# circuit.net
KiCad netlist of a schematic drawn in EAGLE
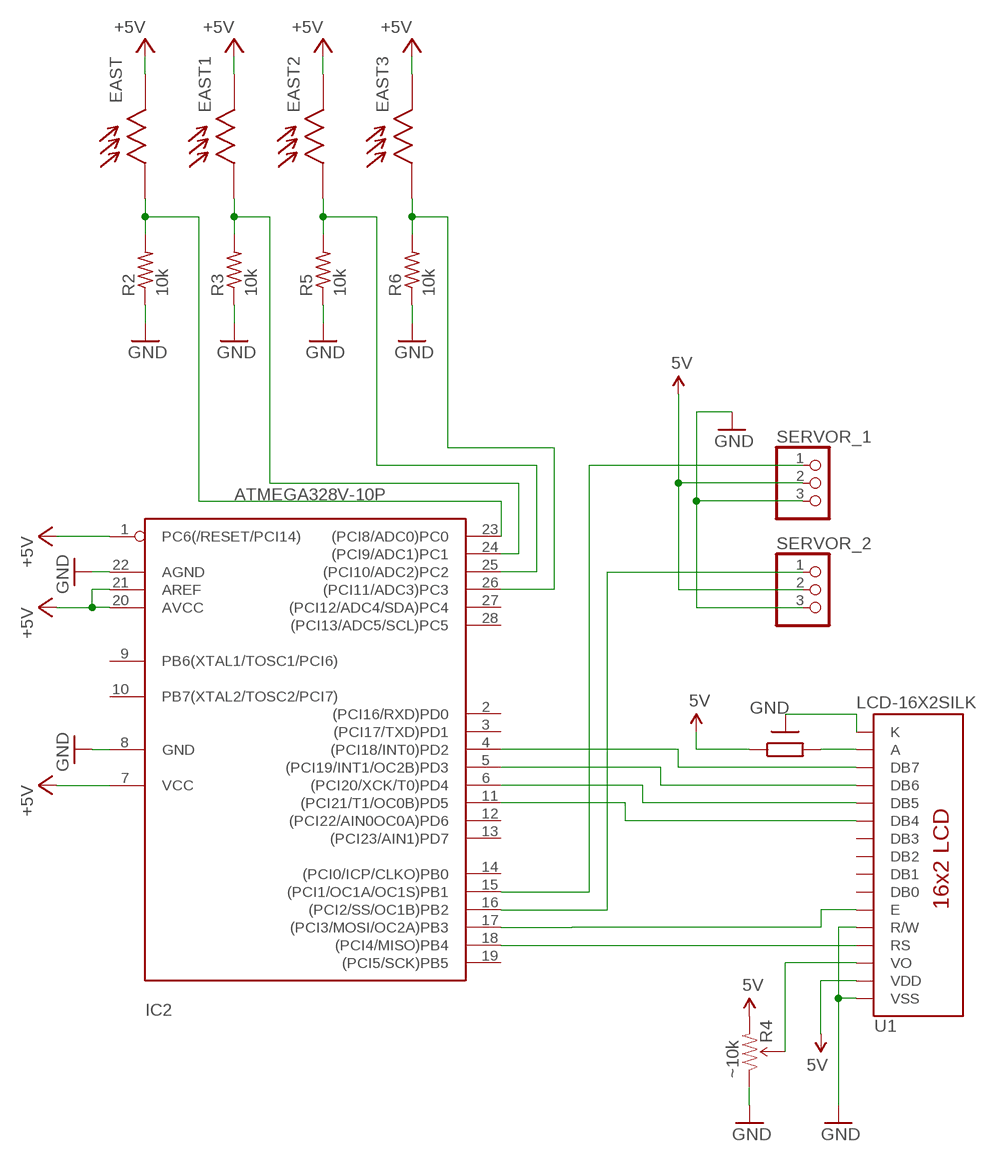
[diagram p0: schematic, sheet 1]

(export (version "E")
  (design (tool "Eeschema 10.0.6"))
  (components
    (comp (ref "EAST")
      (value "CDSLDR3MM")
      (footprint "eagle-import:LDR3MM")
      (libsource (lib "eagle-import") (part "CDSLDR3MM"))
    )
    (comp (ref "EAST1")
      (value "CDSLDR3MM")
      (footprint "eagle-import:LDR3MM")
      (libsource (lib "eagle-import") (part "CDSLDR3MM"))
    )
    (comp (ref "EAST2")
      (value "CDSLDR3MM")
      (footprint "eagle-import:LDR3MM")
      (libsource (lib "eagle-import") (part "CDSLDR3MM"))
    )
    (comp (ref "EAST3")
      (value "CDSLDR3MM")
      (footprint "eagle-import:LDR3MM")
      (libsource (lib "eagle-import") (part "CDSLDR3MM"))
    )
    (comp (ref "IC2")
      (value "ATMEGA328V-10P")
      (footprint "eagle-import:DIL28-3")
      (libsource (lib "eagle-import") (part "ATMEGA328PV-10"))
    )
    (comp (ref "R2")
      (value "10k")
      (footprint "eagle-import:0204_7")
      (libsource (lib "eagle-import") (part "R-US_0204/7"))
    )
    (comp (ref "R3")
      (value "10k")
      (footprint "eagle-import:0204_7")
      (libsource (lib "eagle-import") (part "R-US_0204/7"))
    )
    (comp (ref "R4")
      (value "~10k")
      (footprint "eagle-import:3386U")
      (libsource (lib "eagle-import") (part "TRIMPOT-PTH-KNOB"))
    )
    (comp (ref "R5")
      (value "10k")
      (footprint "eagle-import:0204_7")
      (libsource (lib "eagle-import") (part "R-US_0204/7"))
    )
    (comp (ref "R6")
      (value "10k")
      (footprint "eagle-import:0204_7")
      (libsource (lib "eagle-import") (part "R-US_0204/7"))
    )
    (comp (ref "SERVOR_1")
      (value "PINHD-1X3")
      (footprint "eagle-import:1X03")
      (libsource (lib "eagle-import") (part "PINHD-1X3"))
    )
    (comp (ref "SERVOR_2")
      (value "PINHD-1X3")
      (footprint "eagle-import:1X03")
      (libsource (lib "eagle-import") (part "PINHD-1X3"))
    )
    (comp (ref "U1")
      (value "LCD-16X2SILK")
      (footprint "eagle-import:LCD-16X2")
      (libsource (lib "eagle-import") (part "LCD-16X2SILK"))
    )
  )
  (nets
    (net (code "1") (name "+5V") (class "Default")
      (node (ref "EAST") (pin "P$2") (pinfunction "P$2_P$2") (pintype "bidirectional"))
      (node (ref "EAST1") (pin "P$2") (pinfunction "P$2_P$2") (pintype "bidirectional"))
      (node (ref "EAST2") (pin "P$2") (pinfunction "P$2_P$2") (pintype "bidirectional"))
      (node (ref "EAST3") (pin "P$2") (pinfunction "P$2_P$2") (pintype "bidirectional"))
      (node (ref "IC2") (pin "1") (pinfunction "PC6(/RESET/PCI14)_1") (pintype "bidirectional"))
      (node (ref "IC2") (pin "20") (pinfunction "AVCC_20") (pintype "bidirectional"))
      (node (ref "IC2") (pin "21") (pinfunction "AREF_21") (pintype "bidirectional"))
      (node (ref "IC2") (pin "7") (pinfunction "VCC_7") (pintype "bidirectional"))
    )
    (net (code "2") (name "5V") (class "Default")
      (node (ref "R4") (pin "3") (pinfunction "CW_3") (pintype "passive"))
      (node (ref "SERVOR_1") (pin "2") (pinfunction "2_2") (pintype "passive"))
      (node (ref "SERVOR_2") (pin "2") (pinfunction "2_2") (pintype "passive"))
      (node (ref "U1") (pin "2") (pinfunction "VDD_2") (pintype "power_in"))
    )
    (net (code "3") (name "GND") (class "Default")
      (node (ref "IC2") (pin "22") (pinfunction "AGND_22") (pintype "bidirectional"))
      (node (ref "IC2") (pin "8") (pinfunction "GND_8") (pintype "bidirectional"))
      (node (ref "R2") (pin "1") (pinfunction "1_1") (pintype "passive"))
      (node (ref "R3") (pin "1") (pinfunction "1_1") (pintype "passive"))
      (node (ref "R4") (pin "1") (pinfunction "CCW_1") (pintype "passive"))
      (node (ref "R5") (pin "1") (pinfunction "1_1") (pintype "passive"))
      (node (ref "R6") (pin "1") (pinfunction "1_1") (pintype "passive"))
      (node (ref "SERVOR_1") (pin "3") (pinfunction "3_3") (pintype "passive"))
      (node (ref "SERVOR_2") (pin "3") (pinfunction "3_3") (pintype "passive"))
      (node (ref "U1") (pin "1") (pinfunction "VSS_1") (pintype "power_in"))
      (node (ref "U1") (pin "16") (pinfunction "K_16") (pintype "power_in"))
      (node (ref "U1") (pin "5") (pinfunction "R/W_5") (pintype "input"))
    )
    (net (code "4") (name "Net-(IC2-(PCI1{slash}OC1A{slash}OC1S)PB1)") (class "Default")
      (node (ref "IC2") (pin "15") (pinfunction "(PCI1/OC1A/OC1S)PB1_15") (pintype "bidirectional"))
      (node (ref "SERVOR_1") (pin "1") (pinfunction "1_1") (pintype "passive"))
    )
    (net (code "5") (name "Net-(IC2-(PCI2{slash}SS{slash}OC1B)PB2)") (class "Default")
      (node (ref "IC2") (pin "16") (pinfunction "(PCI2/SS/OC1B)PB2_16") (pintype "bidirectional"))
      (node (ref "SERVOR_2") (pin "1") (pinfunction "1_1") (pintype "passive"))
    )
    (net (code "6") (name "Net-(IC2-(PCI3{slash}MOSI{slash}OC2A)PB3)") (class "Default")
      (node (ref "IC2") (pin "17") (pinfunction "(PCI3/MOSI/OC2A)PB3_17") (pintype "bidirectional"))
      (node (ref "U1") (pin "6") (pinfunction "E_6") (pintype "input"))
    )
    (net (code "7") (name "Net-(IC2-(PCI4{slash}MISO)PB4)") (class "Default")
      (node (ref "IC2") (pin "18") (pinfunction "(PCI4/MISO)PB4_18") (pintype "bidirectional"))
      (node (ref "U1") (pin "4") (pinfunction "RS_4") (pintype "input"))
    )
    (net (code "8") (name "Net-(IC2-(PCI8{slash}ADC0)PC0)") (class "Default")
      (node (ref "EAST") (pin "P$1") (pinfunction "P$1_P$1") (pintype "bidirectional"))
      (node (ref "IC2") (pin "23") (pinfunction "(PCI8/ADC0)PC0_23") (pintype "bidirectional"))
      (node (ref "R2") (pin "2") (pinfunction "2_2") (pintype "passive"))
    )
    (net (code "9") (name "Net-(IC2-(PCI9{slash}ADC1)PC1)") (class "Default")
      (node (ref "EAST1") (pin "P$1") (pinfunction "P$1_P$1") (pintype "bidirectional"))
      (node (ref "IC2") (pin "24") (pinfunction "(PCI9/ADC1)PC1_24") (pintype "bidirectional"))
      (node (ref "R3") (pin "2") (pinfunction "2_2") (pintype "passive"))
    )
    (net (code "10") (name "Net-(IC2-(PCI10{slash}ADC2)PC2)") (class "Default")
      (node (ref "EAST2") (pin "P$1") (pinfunction "P$1_P$1") (pintype "bidirectional"))
      (node (ref "IC2") (pin "25") (pinfunction "(PCI10/ADC2)PC2_25") (pintype "bidirectional"))
      (node (ref "R5") (pin "2") (pinfunction "2_2") (pintype "passive"))
    )
    (net (code "11") (name "Net-(IC2-(PCI11{slash}ADC3)PC3)") (class "Default")
      (node (ref "EAST3") (pin "P$1") (pinfunction "P$1_P$1") (pintype "bidirectional"))
      (node (ref "IC2") (pin "26") (pinfunction "(PCI11/ADC3)PC3_26") (pintype "bidirectional"))
      (node (ref "R6") (pin "2") (pinfunction "2_2") (pintype "passive"))
    )
    (net (code "12") (name "Net-(IC2-(PCI18{slash}INT0)PD2)") (class "Default")
      (node (ref "IC2") (pin "4") (pinfunction "(PCI18/INT0)PD2_4") (pintype "bidirectional"))
      (node (ref "U1") (pin "14") (pinfunction "DB7_14") (pintype "bidirectional"))
    )
    (net (code "13") (name "Net-(IC2-(PCI19{slash}INT1{slash}OC2B)PD3)") (class "Default")
      (node (ref "IC2") (pin "5") (pinfunction "(PCI19/INT1/OC2B)PD3_5") (pintype "bidirectional"))
      (node (ref "U1") (pin "13") (pinfunction "DB6_13") (pintype "bidirectional"))
    )
    (net (code "14") (name "Net-(IC2-(PCI20{slash}XCK{slash}T0)PD4)") (class "Default")
      (node (ref "IC2") (pin "6") (pinfunction "(PCI20/XCK/T0)PD4_6") (pintype "bidirectional"))
      (node (ref "U1") (pin "12") (pinfunction "DB5_12") (pintype "bidirectional"))
    )
    (net (code "15") (name "Net-(IC2-(PCI21{slash}T1{slash}OC0B)PD5)") (class "Default")
      (node (ref "IC2") (pin "11") (pinfunction "(PCI21/T1/OC0B)PD5_11") (pintype "bidirectional"))
      (node (ref "U1") (pin "11") (pinfunction "DB4_11") (pintype "bidirectional"))
    )
    (net (code "16") (name "Net-(R4-WIPER)") (class "Default")
      (node (ref "R4") (pin "2") (pinfunction "WIPER_2") (pintype "passive"))
      (node (ref "U1") (pin "3") (pinfunction "VO_3") (pintype "bidirectional"))
    )
    (net (code "17") (name "unconnected-(IC2-(PCI0{slash}ICP{slash}CLKO)PB0-Pad14)") (class "Default")
      (node (ref "IC2") (pin "14") (pinfunction "(PCI0/ICP/CLKO)PB0_14") (pintype "bidirectional"))
    )
    (net (code "18") (name "unconnected-(IC2-(PCI5{slash}SCK)PB5-Pad19)") (class "Default")
      (node (ref "IC2") (pin "19") (pinfunction "(PCI5/SCK)PB5_19") (pintype "bidirectional"))
    )
    (net (code "19") (name "unconnected-(IC2-(PCI12{slash}ADC4{slash}SDA)PC4-Pad27)") (class "Default")
      (node (ref "IC2") (pin "27") (pinfunction "(PCI12/ADC4/SDA)PC4_27") (pintype "bidirectional"))
    )
    (net (code "20") (name "unconnected-(IC2-(PCI13{slash}ADC5{slash}SCL)PC5-Pad28)") (class "Default")
      (node (ref "IC2") (pin "28") (pinfunction "(PCI13/ADC5/SCL)PC5_28") (pintype "bidirectional"))
    )
    (net (code "21") (name "unconnected-(IC2-(PCI16{slash}RXD)PD0-Pad2)") (class "Default")
      (node (ref "IC2") (pin "2") (pinfunction "(PCI16/RXD)PD0_2") (pintype "bidirectional"))
    )
    (net (code "22") (name "unconnected-(IC2-(PCI17{slash}TXD)PD1-Pad3)") (class "Default")
      (node (ref "IC2") (pin "3") (pinfunction "(PCI17/TXD)PD1_3") (pintype "bidirectional"))
    )
    (net (code "23") (name "unconnected-(IC2-(PCI22{slash}AIN0OC0A)PD6-Pad12)") (class "Default")
      (node (ref "IC2") (pin "12") (pinfunction "(PCI22/AIN0OC0A)PD6_12") (pintype "bidirectional"))
    )
    (net (code "24") (name "unconnected-(IC2-(PCI23{slash}AIN1)PD7-Pad13)") (class "Default")
      (node (ref "IC2") (pin "13") (pinfunction "(PCI23/AIN1)PD7_13") (pintype "bidirectional"))
    )
    (net (code "25") (name "unconnected-(IC2-PB6(XTAL1{slash}TOSC1{slash}PCI6)-Pad9)") (class "Default")
      (node (ref "IC2") (pin "9") (pinfunction "PB6(XTAL1/TOSC1/PCI6)_9") (pintype "bidirectional"))
    )
    (net (code "26") (name "unconnected-(IC2-PB7(XTAL2{slash}TOSC2{slash}PCI7)-Pad10)") (class "Default")
      (node (ref "IC2") (pin "10") (pinfunction "PB7(XTAL2/TOSC2/PCI7)_10") (pintype "bidirectional"))
    )
    (net (code "27") (name "unconnected-(U1-A-Pad15)") (class "Default")
      (node (ref "U1") (pin "15") (pinfunction "A_15") (pintype "power_in"))
    )
    (net (code "28") (name "unconnected-(U1-DB0-Pad7)") (class "Default")
      (node (ref "U1") (pin "7") (pinfunction "DB0_7") (pintype "bidirectional"))
    )
    (net (code "29") (name "unconnected-(U1-DB1-Pad8)") (class "Default")
      (node (ref "U1") (pin "8") (pinfunction "DB1_8") (pintype "bidirectional"))
    )
    (net (code "30") (name "unconnected-(U1-DB2-Pad9)") (class "Default")
      (node (ref "U1") (pin "9") (pinfunction "DB2_9") (pintype "bidirectional"))
    )
    (net (code "31") (name "unconnected-(U1-DB3-Pad10)") (class "Default")
      (node (ref "U1") (pin "10") (pinfunction "DB3_10") (pintype "bidirectional"))
    )
  )
)
